# SCH_CyBorgSPP.net
KiCad netlist of a schematic drawn in EasyEDA
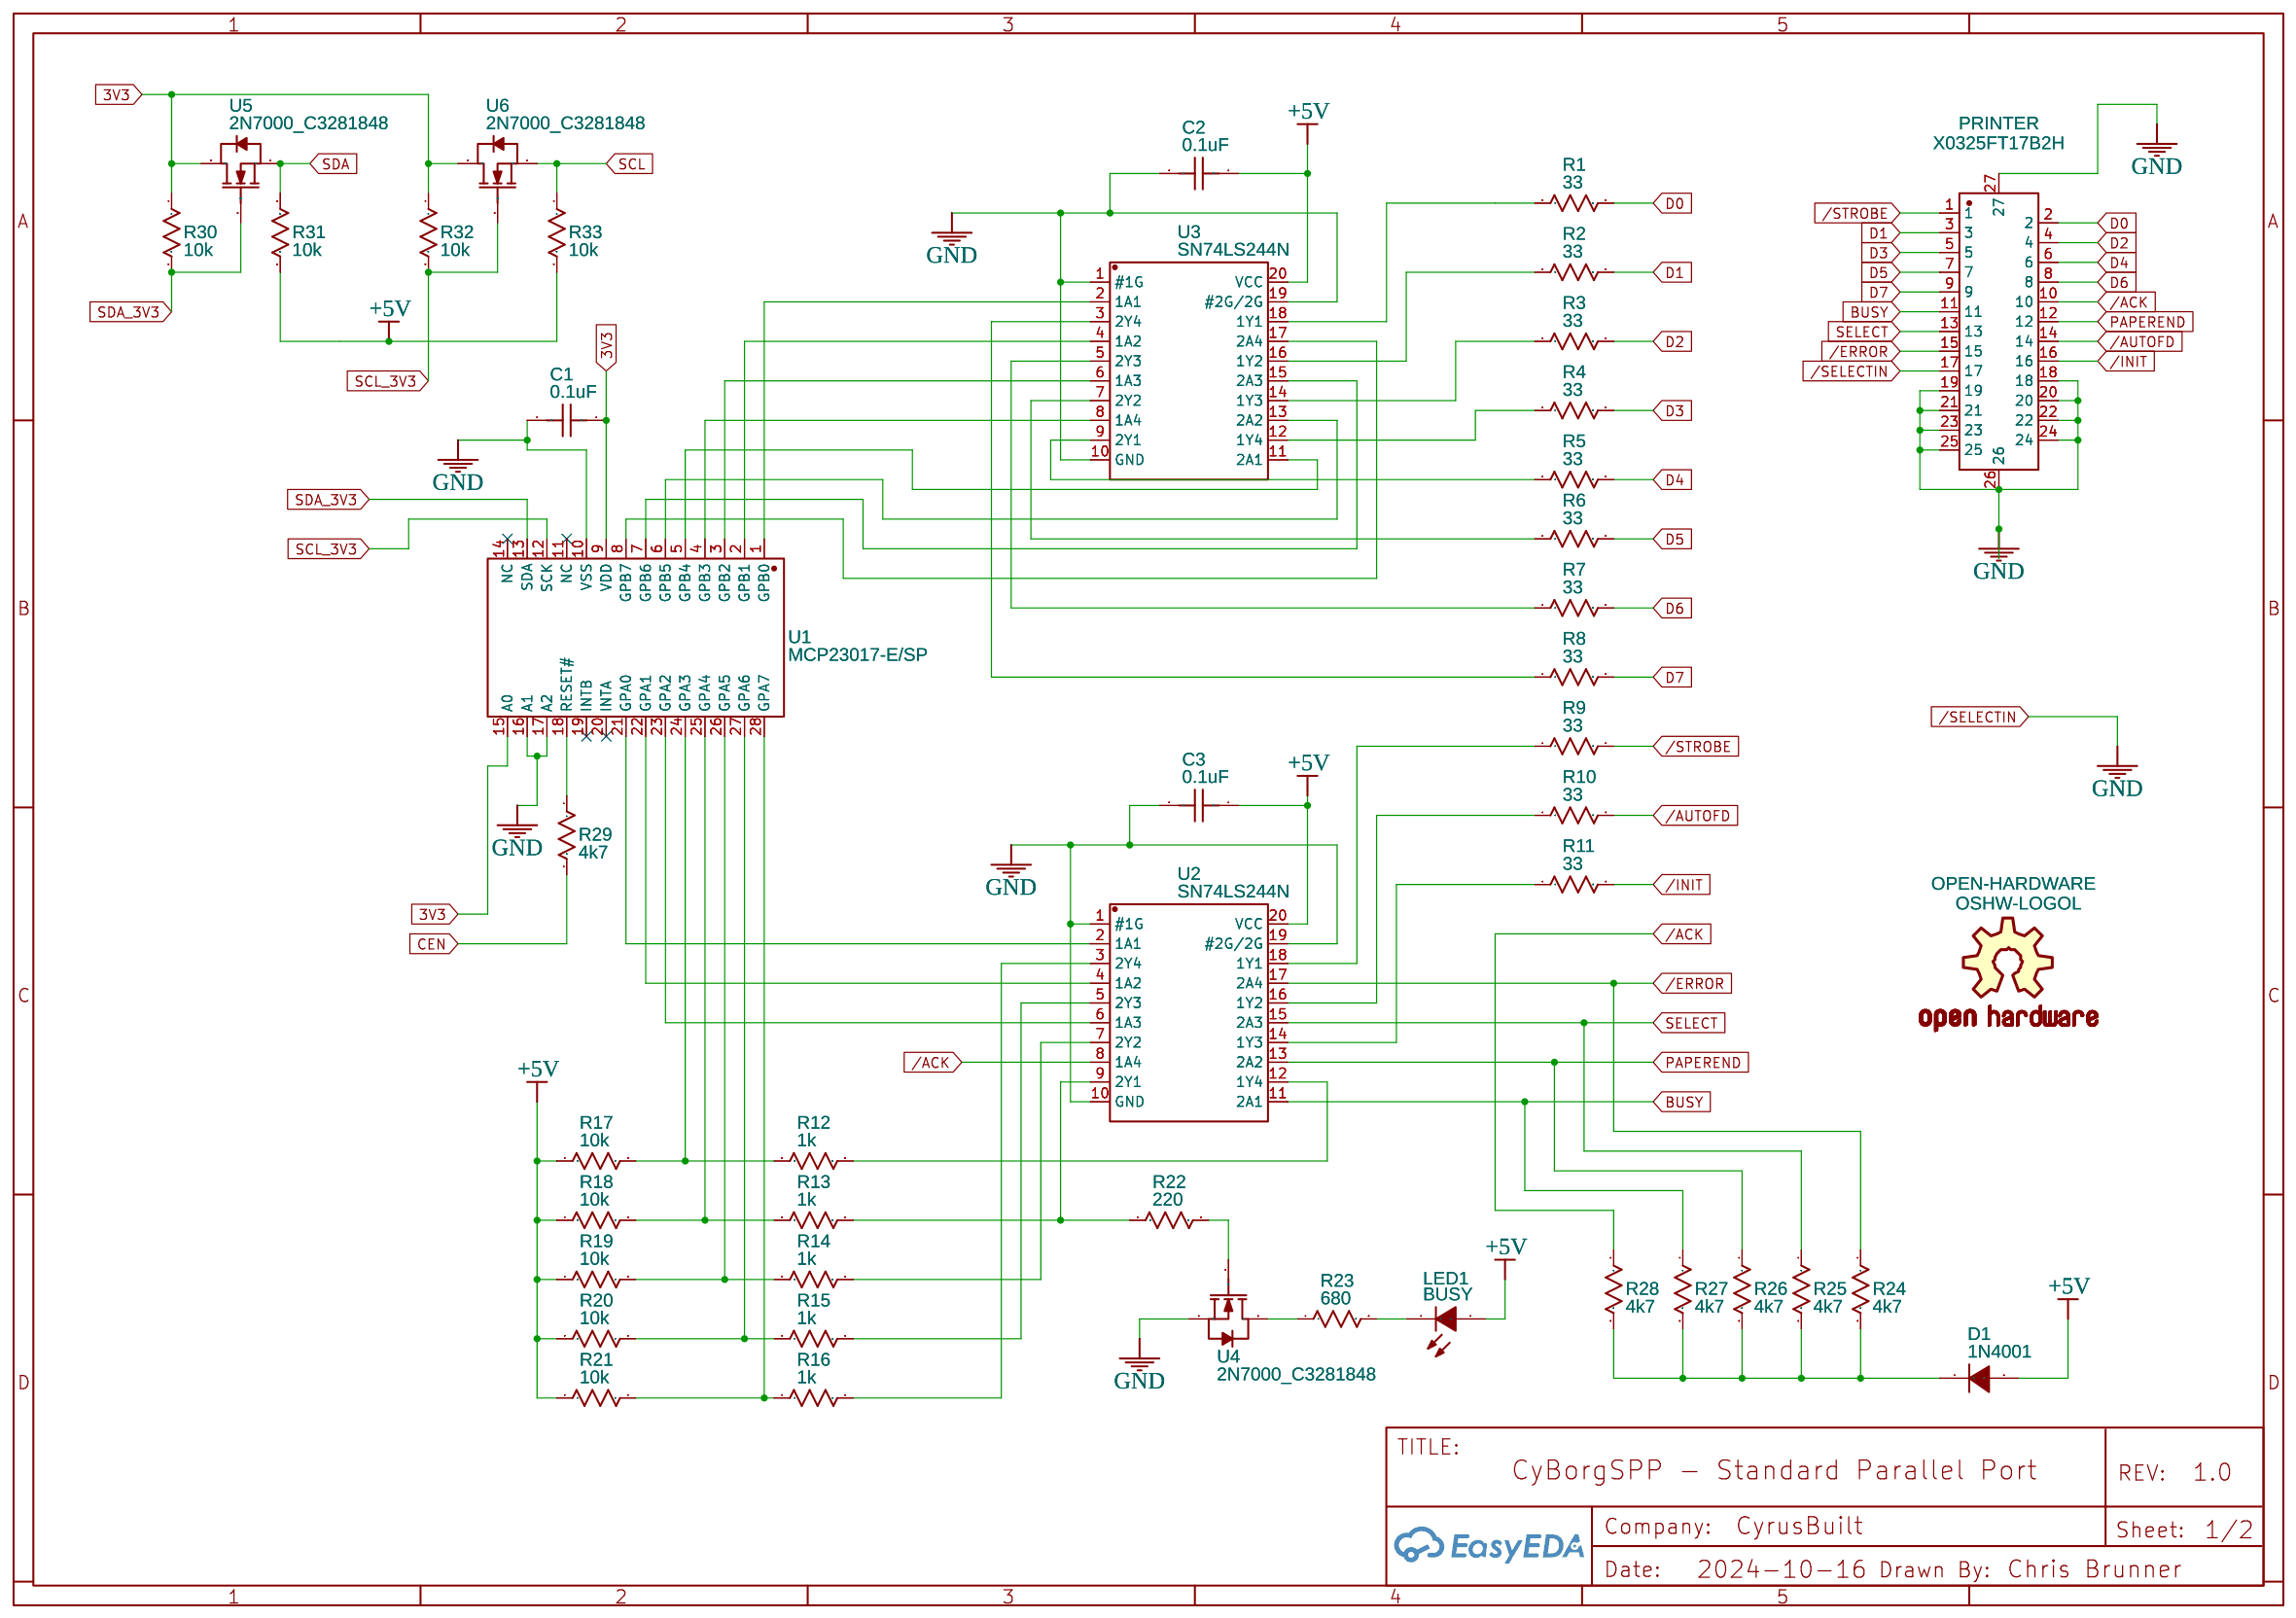
[diagram p0: CyBorgSPP]
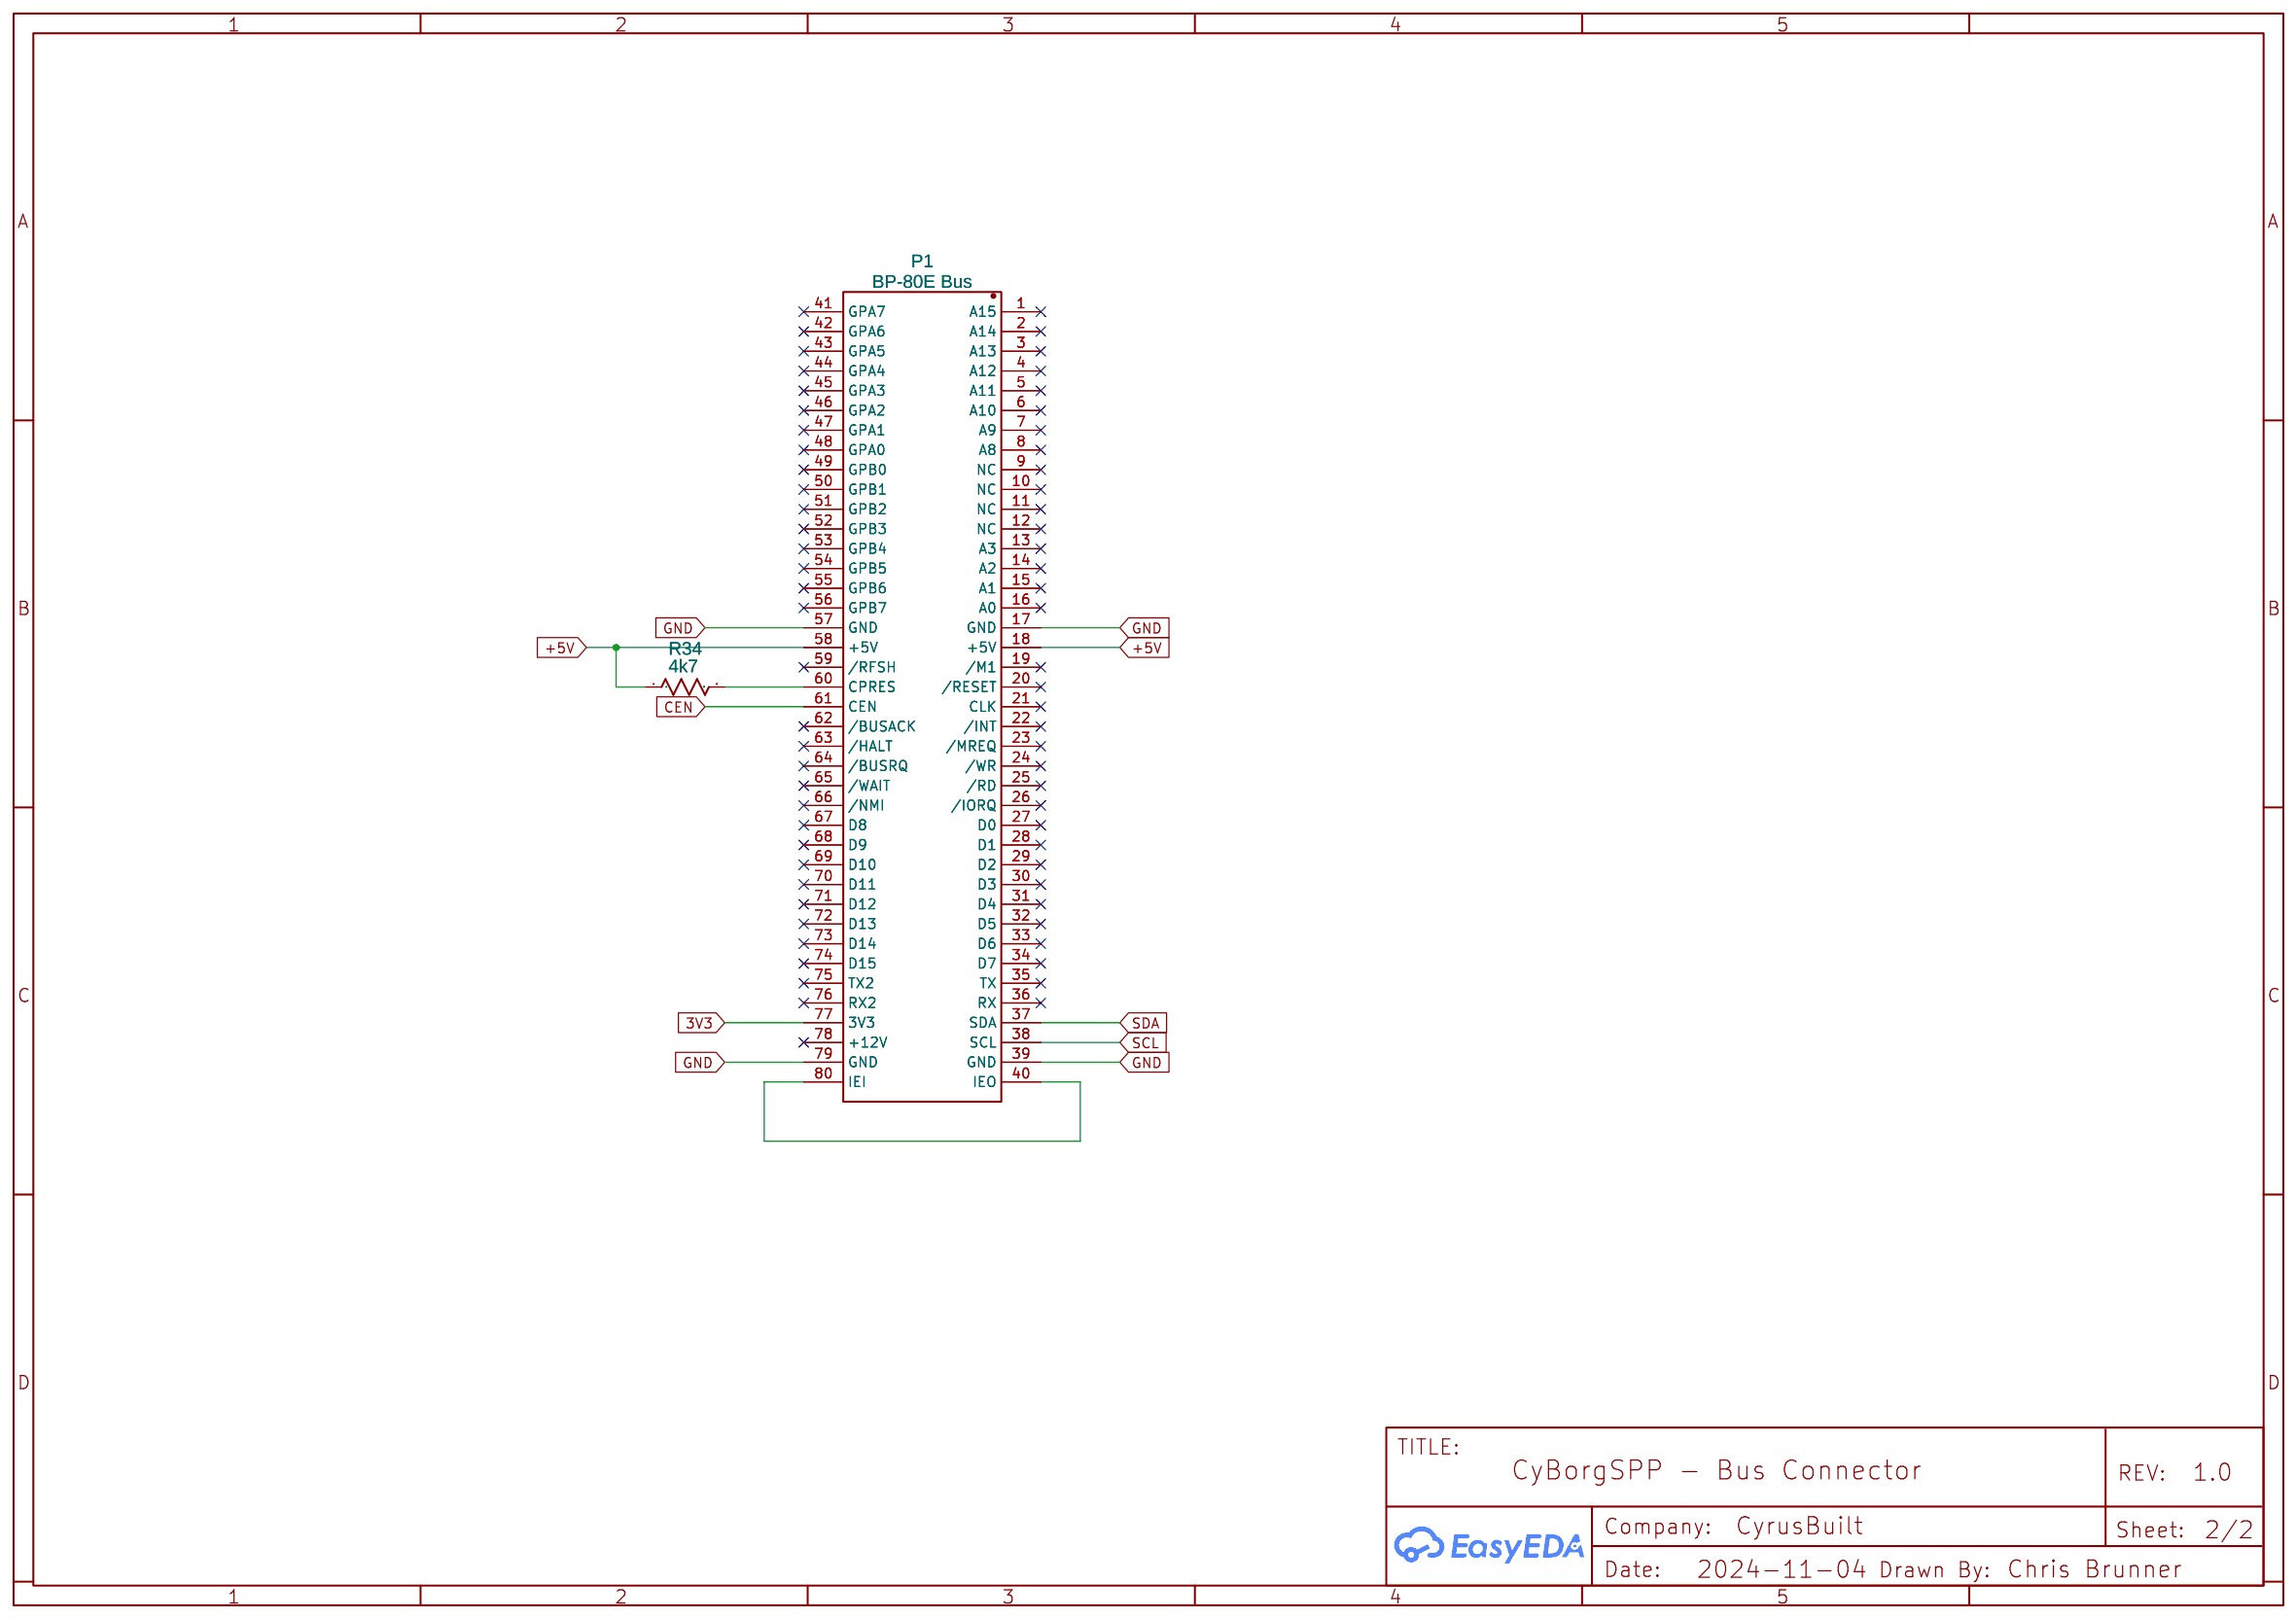
[diagram p1: CyBorgSPP_Bus]

(export (version "E")
  (design (tool "Eeschema 10.0.6"))
  (components
    (comp (ref "C1") (value "0.1uF") (libsource (lib "") (part "C_0603_US")))
    (comp (ref "C2") (value "0.1uF") (libsource (lib "") (part "C_0603_US")))
    (comp (ref "C3") (value "0.1uF") (libsource (lib "") (part "C_0603_US")))
    (comp (ref "D1")
      (value "1N4001")
      (fields (field (name "Manufacturer") "LRC"))
      (libsource (lib "") (part "1N4001"))
    )
    (comp (ref "LED1")
      (value "BUSY")
      (fields
        (field (name "Manufacturer Part") "204-10SURD/S530-A3")
        (field (name "Manufacturer") "EVERLIGHT(亿光)")
      )
      (libsource (lib "") (part "204-10SURD/S530-A3"))
    )
    (comp (ref "OPEN-HARDWARE") (value "OSHW-LOGOL") (libsource (lib "") (part "OSHW-LOGOL")))
    (comp (ref "PRINTER")
      (value "X0325FT17B2H")
      (fields (field (name "Manufacturer") "XKB Connectivity(中国星坤)"))
      (libsource (lib "") (part "X0325FT17B2H"))
    )
    (comp (ref "R1")
      (value "33")
      (fields (field (name "Manufacturer Part") "MCF 0.25W 150R") (field (name "Manufacturer") "MULTICOMP"))
      (libsource (lib "") (part "MCF 0.25W 150R"))
    )
    (comp (ref "R2")
      (value "33")
      (fields (field (name "Manufacturer Part") "MCF 0.25W 150R") (field (name "Manufacturer") "MULTICOMP"))
      (libsource (lib "") (part "MCF 0.25W 150R"))
    )
    (comp (ref "R3")
      (value "33")
      (fields (field (name "Manufacturer Part") "MCF 0.25W 150R") (field (name "Manufacturer") "MULTICOMP"))
      (libsource (lib "") (part "MCF 0.25W 150R"))
    )
    (comp (ref "R4")
      (value "33")
      (fields (field (name "Manufacturer Part") "MCF 0.25W 150R") (field (name "Manufacturer") "MULTICOMP"))
      (libsource (lib "") (part "MCF 0.25W 150R"))
    )
    (comp (ref "R5")
      (value "33")
      (fields (field (name "Manufacturer Part") "MCF 0.25W 150R") (field (name "Manufacturer") "MULTICOMP"))
      (libsource (lib "") (part "MCF 0.25W 150R"))
    )
    (comp (ref "R6")
      (value "33")
      (fields (field (name "Manufacturer Part") "MCF 0.25W 150R") (field (name "Manufacturer") "MULTICOMP"))
      (libsource (lib "") (part "MCF 0.25W 150R"))
    )
    (comp (ref "R7")
      (value "33")
      (fields (field (name "Manufacturer Part") "MCF 0.25W 150R") (field (name "Manufacturer") "MULTICOMP"))
      (libsource (lib "") (part "MCF 0.25W 150R"))
    )
    (comp (ref "R8")
      (value "33")
      (fields (field (name "Manufacturer Part") "MCF 0.25W 150R") (field (name "Manufacturer") "MULTICOMP"))
      (libsource (lib "") (part "MCF 0.25W 150R"))
    )
    (comp (ref "R9")
      (value "33")
      (fields (field (name "Manufacturer Part") "MCF 0.25W 150R") (field (name "Manufacturer") "MULTICOMP"))
      (libsource (lib "") (part "MCF 0.25W 150R"))
    )
    (comp (ref "R10")
      (value "33")
      (fields (field (name "Manufacturer Part") "MCF 0.25W 150R") (field (name "Manufacturer") "MULTICOMP"))
      (libsource (lib "") (part "MCF 0.25W 150R"))
    )
    (comp (ref "R11")
      (value "33")
      (fields (field (name "Manufacturer Part") "MCF 0.25W 150R") (field (name "Manufacturer") "MULTICOMP"))
      (libsource (lib "") (part "MCF 0.25W 150R"))
    )
    (comp (ref "R12")
      (value "1k")
      (fields (field (name "Manufacturer Part") "MCF 0.25W 150R") (field (name "Manufacturer") "MULTICOMP"))
      (libsource (lib "") (part "MCF 0.25W 150R"))
    )
    (comp (ref "R13")
      (value "1k")
      (fields (field (name "Manufacturer Part") "MCF 0.25W 150R") (field (name "Manufacturer") "MULTICOMP"))
      (libsource (lib "") (part "MCF 0.25W 150R"))
    )
    (comp (ref "R14")
      (value "1k")
      (fields (field (name "Manufacturer Part") "MCF 0.25W 150R") (field (name "Manufacturer") "MULTICOMP"))
      (libsource (lib "") (part "MCF 0.25W 150R"))
    )
    (comp (ref "R15")
      (value "1k")
      (fields (field (name "Manufacturer Part") "MCF 0.25W 150R") (field (name "Manufacturer") "MULTICOMP"))
      (libsource (lib "") (part "MCF 0.25W 150R"))
    )
    (comp (ref "R16")
      (value "1k")
      (fields (field (name "Manufacturer Part") "MCF 0.25W 150R") (field (name "Manufacturer") "MULTICOMP"))
      (libsource (lib "") (part "MCF 0.25W 150R"))
    )
    (comp (ref "R17")
      (value "10k")
      (fields (field (name "Manufacturer Part") "MCF 0.25W 150R") (field (name "Manufacturer") "MULTICOMP"))
      (libsource (lib "") (part "MCF 0.25W 150R"))
    )
    (comp (ref "R18")
      (value "10k")
      (fields (field (name "Manufacturer Part") "MCF 0.25W 150R") (field (name "Manufacturer") "MULTICOMP"))
      (libsource (lib "") (part "MCF 0.25W 150R"))
    )
    (comp (ref "R19")
      (value "10k")
      (fields (field (name "Manufacturer Part") "MCF 0.25W 150R") (field (name "Manufacturer") "MULTICOMP"))
      (libsource (lib "") (part "MCF 0.25W 150R"))
    )
    (comp (ref "R20")
      (value "10k")
      (fields (field (name "Manufacturer Part") "MCF 0.25W 150R") (field (name "Manufacturer") "MULTICOMP"))
      (libsource (lib "") (part "MCF 0.25W 150R"))
    )
    (comp (ref "R21")
      (value "10k")
      (fields (field (name "Manufacturer Part") "MCF 0.25W 150R") (field (name "Manufacturer") "MULTICOMP"))
      (libsource (lib "") (part "MCF 0.25W 150R"))
    )
    (comp (ref "R22")
      (value "220")
      (fields (field (name "Manufacturer Part") "MCF 0.25W 150R") (field (name "Manufacturer") "MULTICOMP"))
      (libsource (lib "") (part "MCF 0.25W 150R"))
    )
    (comp (ref "R23")
      (value "680")
      (fields (field (name "Manufacturer Part") "MCF 0.25W 150R") (field (name "Manufacturer") "MULTICOMP"))
      (libsource (lib "") (part "MCF 0.25W 150R"))
    )
    (comp (ref "R24")
      (value "4k7")
      (fields (field (name "Manufacturer Part") "MCF 0.25W 150R") (field (name "Manufacturer") "MULTICOMP"))
      (libsource (lib "") (part "MCF 0.25W 150R_1"))
    )
    (comp (ref "R25")
      (value "4k7")
      (fields (field (name "Manufacturer Part") "MCF 0.25W 150R") (field (name "Manufacturer") "MULTICOMP"))
      (libsource (lib "") (part "MCF 0.25W 150R_1"))
    )
    (comp (ref "R26")
      (value "4k7")
      (fields (field (name "Manufacturer Part") "MCF 0.25W 150R") (field (name "Manufacturer") "MULTICOMP"))
      (libsource (lib "") (part "MCF 0.25W 150R_1"))
    )
    (comp (ref "R27")
      (value "4k7")
      (fields (field (name "Manufacturer Part") "MCF 0.25W 150R") (field (name "Manufacturer") "MULTICOMP"))
      (libsource (lib "") (part "MCF 0.25W 150R_1"))
    )
    (comp (ref "R28")
      (value "4k7")
      (fields (field (name "Manufacturer Part") "MCF 0.25W 150R") (field (name "Manufacturer") "MULTICOMP"))
      (libsource (lib "") (part "MCF 0.25W 150R_1"))
    )
    (comp (ref "R29")
      (value "4k7")
      (fields (field (name "Manufacturer Part") "MCF 0.25W 150R") (field (name "Manufacturer") "MULTICOMP"))
      (libsource (lib "") (part "MCF 0.25W 150R_1"))
    )
    (comp (ref "R30")
      (value "10k")
      (fields (field (name "Manufacturer Part") "MCF 0.25W 150R") (field (name "Manufacturer") "MULTICOMP"))
      (libsource (lib "") (part "MCF 0.25W 150R_1"))
    )
    (comp (ref "R31")
      (value "10k")
      (fields (field (name "Manufacturer Part") "MCF 0.25W 150R") (field (name "Manufacturer") "MULTICOMP"))
      (libsource (lib "") (part "MCF 0.25W 150R_1"))
    )
    (comp (ref "R32")
      (value "10k")
      (fields (field (name "Manufacturer Part") "MCF 0.25W 150R") (field (name "Manufacturer") "MULTICOMP"))
      (libsource (lib "") (part "MCF 0.25W 150R_1"))
    )
    (comp (ref "R33")
      (value "10k")
      (fields (field (name "Manufacturer Part") "MCF 0.25W 150R") (field (name "Manufacturer") "MULTICOMP"))
      (libsource (lib "") (part "MCF 0.25W 150R_1"))
    )
    (comp (ref "U1")
      (value "MCP23017-E/SP")
      (fields (field (name "Manufacturer") "Microchip Tech"))
      (libsource (lib "") (part "MCP23017-E/SP"))
    )
    (comp (ref "U2")
      (value "SN74LS244N")
      (fields (field (name "Manufacturer") "TI(德州仪器)"))
      (libsource (lib "") (part "SN74LS244N"))
    )
    (comp (ref "U3")
      (value "SN74LS244N")
      (fields (field (name "Manufacturer") "TI(德州仪器)"))
      (libsource (lib "") (part "SN74LS244N"))
    )
    (comp (ref "U4")
      (value "2N7000_C3281848")
      (fields (field (name "Manufacturer Part") "2N7000") (field (name "Manufacturer") "DIOTEC(德欧泰克)"))
      (libsource (lib "") (part "2N7000_C3281848_1"))
    )
    (comp (ref "U5")
      (value "2N7000_C3281848")
      (fields (field (name "Manufacturer Part") "2N7000") (field (name "Manufacturer") "DIOTEC(德欧泰克)"))
      (libsource (lib "") (part "2N7000_C3281848"))
    )
    (comp (ref "U6")
      (value "2N7000_C3281848")
      (fields (field (name "Manufacturer Part") "2N7000") (field (name "Manufacturer") "DIOTEC(德欧泰克)"))
      (libsource (lib "") (part "2N7000_C3281848"))
    )
    (comp (ref "P1")
      (value "BP-80E Bus")
      (fields
        (field (name "Manufacturer Part") "ReliaPro")
        (field (name "Manufacturer") "2.54mm 1x40T Female header")
      )
      (libsource (lib "") (part "Extended Backplane 2x40 Male Angled"))
    )
    (comp (ref "R34")
      (value "4k7")
      (fields (field (name "Manufacturer Part") "MCF 0.25W 150R") (field (name "Manufacturer") "MULTICOMP"))
      (libsource (lib "") (part "MCF 0.25W 150R"))
    )
  )
  (nets
    (net (code "1") (name "+5V") (class "Default")
      (node (ref "C2") (pin "1") (pinfunction "1_1") (pintype "unspecified"))
      (node (ref "C3") (pin "1") (pinfunction "1_1") (pintype "unspecified"))
      (node (ref "D1") (pin "2") (pinfunction "A_2") (pintype "unspecified"))
      (node (ref "LED1") (pin "1") (pinfunction "A_1") (pintype "input"))
      (node (ref "P1") (pin "18") (pinfunction "+5V_18") (pintype "unspecified"))
      (node (ref "P1") (pin "58") (pinfunction "+5V_58") (pintype "unspecified"))
      (node (ref "R17") (pin "1") (pinfunction "1_1") (pintype "unspecified"))
      (node (ref "R18") (pin "1") (pinfunction "1_1") (pintype "unspecified"))
      (node (ref "R19") (pin "1") (pinfunction "1_1") (pintype "unspecified"))
      (node (ref "R20") (pin "1") (pinfunction "1_1") (pintype "unspecified"))
      (node (ref "R21") (pin "1") (pinfunction "1_1") (pintype "unspecified"))
      (node (ref "R31") (pin "2") (pinfunction "2_2") (pintype "unspecified"))
      (node (ref "R33") (pin "2") (pinfunction "2_2") (pintype "unspecified"))
      (node (ref "R34") (pin "1") (pinfunction "1_1") (pintype "unspecified"))
      (node (ref "U2") (pin "20") (pinfunction "VCC_20") (pintype "unspecified"))
      (node (ref "U3") (pin "20") (pinfunction "VCC_20") (pintype "unspecified"))
    )
    (net (code "2") (name "3V3") (class "Default")
      (node (ref "C1") (pin "1") (pinfunction "1_1") (pintype "unspecified"))
      (node (ref "P1") (pin "77") (pinfunction "3V3_77") (pintype "unspecified"))
      (node (ref "R30") (pin "1") (pinfunction "1_1") (pintype "unspecified"))
      (node (ref "R32") (pin "1") (pinfunction "1_1") (pintype "unspecified"))
      (node (ref "U1") (pin "15") (pinfunction "A0_15") (pintype "unspecified"))
      (node (ref "U1") (pin "9") (pinfunction "VDD_9") (pintype "unspecified"))
      (node (ref "U5") (pin "3") (pinfunction "D_3") (pintype "unspecified"))
      (node (ref "U6") (pin "3") (pinfunction "D_3") (pintype "unspecified"))
    )
    (net (code "3") (name "BUSY") (class "Default")
      (node (ref "PRINTER") (pin "11") (pinfunction "11_11") (pintype "unspecified"))
      (node (ref "R27") (pin "1") (pinfunction "1_1") (pintype "unspecified"))
      (node (ref "U2") (pin "11") (pinfunction "2A1_11") (pintype "unspecified"))
    )
    (net (code "4") (name "CEN") (class "Default")
      (node (ref "P1") (pin "61") (pinfunction "CEN_61") (pintype "unspecified"))
      (node (ref "R29") (pin "2") (pinfunction "2_2") (pintype "unspecified"))
    )
    (net (code "5") (name "D0") (class "Default")
      (node (ref "PRINTER") (pin "2") (pinfunction "2_2") (pintype "unspecified"))
      (node (ref "R1") (pin "2") (pinfunction "2_2") (pintype "unspecified"))
    )
    (net (code "6") (name "D1") (class "Default")
      (node (ref "PRINTER") (pin "3") (pinfunction "3_3") (pintype "unspecified"))
      (node (ref "R2") (pin "2") (pinfunction "2_2") (pintype "unspecified"))
    )
    (net (code "7") (name "D2") (class "Default")
      (node (ref "PRINTER") (pin "4") (pinfunction "4_4") (pintype "unspecified"))
      (node (ref "R3") (pin "2") (pinfunction "2_2") (pintype "unspecified"))
    )
    (net (code "8") (name "D3") (class "Default")
      (node (ref "PRINTER") (pin "5") (pinfunction "5_5") (pintype "unspecified"))
      (node (ref "R4") (pin "2") (pinfunction "2_2") (pintype "unspecified"))
    )
    (net (code "9") (name "D4") (class "Default")
      (node (ref "PRINTER") (pin "6") (pinfunction "6_6") (pintype "unspecified"))
      (node (ref "R5") (pin "2") (pinfunction "2_2") (pintype "unspecified"))
    )
    (net (code "10") (name "D5") (class "Default")
      (node (ref "PRINTER") (pin "7") (pinfunction "7_7") (pintype "unspecified"))
      (node (ref "R6") (pin "2") (pinfunction "2_2") (pintype "unspecified"))
    )
    (net (code "11") (name "D6") (class "Default")
      (node (ref "PRINTER") (pin "8") (pinfunction "8_8") (pintype "unspecified"))
      (node (ref "R7") (pin "2") (pinfunction "2_2") (pintype "unspecified"))
    )
    (net (code "12") (name "D7") (class "Default")
      (node (ref "PRINTER") (pin "9") (pinfunction "9_9") (pintype "unspecified"))
      (node (ref "R8") (pin "2") (pinfunction "2_2") (pintype "unspecified"))
    )
    (net (code "13") (name "GND") (class "Default")
      (node (ref "C1") (pin "2") (pinfunction "2_2") (pintype "unspecified"))
      (node (ref "C2") (pin "2") (pinfunction "2_2") (pintype "unspecified"))
      (node (ref "C3") (pin "2") (pinfunction "2_2") (pintype "unspecified"))
      (node (ref "P1") (pin "17") (pinfunction "GND_17") (pintype "unspecified"))
      (node (ref "P1") (pin "39") (pinfunction "GND_39") (pintype "unspecified"))
      (node (ref "P1") (pin "57") (pinfunction "GND_57") (pintype "unspecified"))
      (node (ref "P1") (pin "79") (pinfunction "GND_79") (pintype "unspecified"))
      (node (ref "PRINTER") (pin "17") (pinfunction "17_17") (pintype "unspecified"))
      (node (ref "PRINTER") (pin "18") (pinfunction "18_18") (pintype "unspecified"))
      (node (ref "PRINTER") (pin "19") (pinfunction "19_19") (pintype "unspecified"))
      (node (ref "PRINTER") (pin "20") (pinfunction "20_20") (pintype "unspecified"))
      (node (ref "PRINTER") (pin "21") (pinfunction "21_21") (pintype "unspecified"))
      (node (ref "PRINTER") (pin "22") (pinfunction "22_22") (pintype "unspecified"))
      (node (ref "PRINTER") (pin "23") (pinfunction "23_23") (pintype "unspecified"))
      (node (ref "PRINTER") (pin "24") (pinfunction "24_24") (pintype "unspecified"))
      (node (ref "PRINTER") (pin "25") (pinfunction "25_25") (pintype "unspecified"))
      (node (ref "PRINTER") (pin "26") (pinfunction "26_26") (pintype "unspecified"))
      (node (ref "PRINTER") (pin "27") (pinfunction "27_27") (pintype "unspecified"))
      (node (ref "U1") (pin "10") (pinfunction "VSS_10") (pintype "unspecified"))
      (node (ref "U1") (pin "16") (pinfunction "A1_16") (pintype "unspecified"))
      (node (ref "U1") (pin "17") (pinfunction "A2_17") (pintype "unspecified"))
      (node (ref "U2") (pin "1") (pinfunction "#1G_1") (pintype "unspecified"))
      (node (ref "U2") (pin "10") (pinfunction "GND_10") (pintype "unspecified"))
      (node (ref "U2") (pin "19") (pinfunction "#2G/2G_19") (pintype "unspecified"))
      (node (ref "U3") (pin "1") (pinfunction "#1G_1") (pintype "unspecified"))
      (node (ref "U3") (pin "10") (pinfunction "GND_10") (pintype "unspecified"))
      (node (ref "U3") (pin "19") (pinfunction "#2G/2G_19") (pintype "unspecified"))
      (node (ref "U4") (pin "1") (pinfunction "S_1") (pintype "unspecified"))
    )
    (net (code "14") (name "Net-(D1-K)") (class "Default")
      (node (ref "D1") (pin "1") (pinfunction "K_1") (pintype "unspecified"))
      (node (ref "R24") (pin "2") (pinfunction "2_2") (pintype "unspecified"))
      (node (ref "R25") (pin "2") (pinfunction "2_2") (pintype "unspecified"))
      (node (ref "R26") (pin "2") (pinfunction "2_2") (pintype "unspecified"))
      (node (ref "R27") (pin "2") (pinfunction "2_2") (pintype "unspecified"))
      (node (ref "R28") (pin "2") (pinfunction "2_2") (pintype "unspecified"))
    )
    (net (code "15") (name "Net-(LED1-K)") (class "Default")
      (node (ref "LED1") (pin "2") (pinfunction "K_2") (pintype "input"))
      (node (ref "R23") (pin "2") (pinfunction "2_2") (pintype "unspecified"))
    )
    (net (code "16") (name "Net-(P1-CPRES)") (class "Default")
      (node (ref "P1") (pin "60") (pinfunction "CPRES_60") (pintype "unspecified"))
      (node (ref "R34") (pin "2") (pinfunction "2_2") (pintype "unspecified"))
    )
    (net (code "17") (name "Net-(P1-IEI)") (class "Default")
      (node (ref "P1") (pin "40") (pinfunction "IEO_40") (pintype "unspecified"))
      (node (ref "P1") (pin "80") (pinfunction "IEI_80") (pintype "unspecified"))
    )
    (net (code "18") (name "Net-(U1-GPA0)") (class "Default")
      (node (ref "U1") (pin "21") (pinfunction "GPA0_21") (pintype "unspecified"))
      (node (ref "U2") (pin "2") (pinfunction "1A1_2") (pintype "unspecified"))
    )
    (net (code "19") (name "Net-(U1-GPA1)") (class "Default")
      (node (ref "U1") (pin "22") (pinfunction "GPA1_22") (pintype "unspecified"))
      (node (ref "U2") (pin "4") (pinfunction "1A2_4") (pintype "unspecified"))
    )
    (net (code "20") (name "Net-(U1-GPA2)") (class "Default")
      (node (ref "U1") (pin "23") (pinfunction "GPA2_23") (pintype "unspecified"))
      (node (ref "U2") (pin "6") (pinfunction "1A3_6") (pintype "unspecified"))
    )
    (net (code "21") (name "Net-(U1-GPA3)") (class "Default")
      (node (ref "R12") (pin "1") (pinfunction "1_1") (pintype "unspecified"))
      (node (ref "R17") (pin "2") (pinfunction "2_2") (pintype "unspecified"))
      (node (ref "U1") (pin "24") (pinfunction "GPA3_24") (pintype "unspecified"))
    )
    (net (code "22") (name "Net-(U1-GPA4)") (class "Default")
      (node (ref "R13") (pin "1") (pinfunction "1_1") (pintype "unspecified"))
      (node (ref "R18") (pin "2") (pinfunction "2_2") (pintype "unspecified"))
      (node (ref "U1") (pin "25") (pinfunction "GPA4_25") (pintype "unspecified"))
    )
    (net (code "23") (name "Net-(U1-GPA5)") (class "Default")
      (node (ref "R14") (pin "1") (pinfunction "1_1") (pintype "unspecified"))
      (node (ref "R19") (pin "2") (pinfunction "2_2") (pintype "unspecified"))
      (node (ref "U1") (pin "26") (pinfunction "GPA5_26") (pintype "unspecified"))
    )
    (net (code "24") (name "Net-(U1-GPA6)") (class "Default")
      (node (ref "R15") (pin "1") (pinfunction "1_1") (pintype "unspecified"))
      (node (ref "R20") (pin "2") (pinfunction "2_2") (pintype "unspecified"))
      (node (ref "U1") (pin "27") (pinfunction "GPA6_27") (pintype "unspecified"))
    )
    (net (code "25") (name "Net-(U1-GPA7)") (class "Default")
      (node (ref "R16") (pin "1") (pinfunction "1_1") (pintype "unspecified"))
      (node (ref "R21") (pin "2") (pinfunction "2_2") (pintype "unspecified"))
      (node (ref "U1") (pin "28") (pinfunction "GPA7_28") (pintype "unspecified"))
    )
    (net (code "26") (name "Net-(U1-GPB0)") (class "Default")
      (node (ref "U1") (pin "1") (pinfunction "GPB0_1") (pintype "unspecified"))
      (node (ref "U3") (pin "2") (pinfunction "1A1_2") (pintype "unspecified"))
    )
    (net (code "27") (name "Net-(U1-GPB1)") (class "Default")
      (node (ref "U1") (pin "2") (pinfunction "GPB1_2") (pintype "unspecified"))
      (node (ref "U3") (pin "4") (pinfunction "1A2_4") (pintype "unspecified"))
    )
    (net (code "28") (name "Net-(U1-GPB2)") (class "Default")
      (node (ref "U1") (pin "3") (pinfunction "GPB2_3") (pintype "unspecified"))
      (node (ref "U3") (pin "6") (pinfunction "1A3_6") (pintype "unspecified"))
    )
    (net (code "29") (name "Net-(U1-GPB3)") (class "Default")
      (node (ref "U1") (pin "4") (pinfunction "GPB3_4") (pintype "unspecified"))
      (node (ref "U3") (pin "8") (pinfunction "1A4_8") (pintype "unspecified"))
    )
    (net (code "30") (name "Net-(U1-GPB4)") (class "Default")
      (node (ref "U1") (pin "5") (pinfunction "GPB4_5") (pintype "unspecified"))
      (node (ref "U3") (pin "11") (pinfunction "2A1_11") (pintype "unspecified"))
    )
    (net (code "31") (name "Net-(U1-GPB5)") (class "Default")
      (node (ref "U1") (pin "6") (pinfunction "GPB5_6") (pintype "unspecified"))
      (node (ref "U3") (pin "13") (pinfunction "2A2_13") (pintype "unspecified"))
    )
    (net (code "32") (name "Net-(U1-GPB6)") (class "Default")
      (node (ref "U1") (pin "7") (pinfunction "GPB6_7") (pintype "unspecified"))
      (node (ref "U3") (pin "15") (pinfunction "2A3_15") (pintype "unspecified"))
    )
    (net (code "33") (name "Net-(U1-GPB7)") (class "Default")
      (node (ref "U1") (pin "8") (pinfunction "GPB7_8") (pintype "unspecified"))
      (node (ref "U3") (pin "17") (pinfunction "2A4_17") (pintype "unspecified"))
    )
    (net (code "34") (name "Net-(U1-RESET#)") (class "Default")
      (node (ref "R29") (pin "1") (pinfunction "1_1") (pintype "unspecified"))
      (node (ref "U1") (pin "18") (pinfunction "RESET#_18") (pintype "unspecified"))
    )
    (net (code "35") (name "Net-(U2-1Y1)") (class "Default")
      (node (ref "R9") (pin "1") (pinfunction "1_1") (pintype "unspecified"))
      (node (ref "U2") (pin "18") (pinfunction "1Y1_18") (pintype "unspecified"))
    )
    (net (code "36") (name "Net-(U2-1Y2)") (class "Default")
      (node (ref "R10") (pin "1") (pinfunction "1_1") (pintype "unspecified"))
      (node (ref "U2") (pin "16") (pinfunction "1Y2_16") (pintype "unspecified"))
    )
    (net (code "37") (name "Net-(U2-1Y3)") (class "Default")
      (node (ref "R11") (pin "1") (pinfunction "1_1") (pintype "unspecified"))
      (node (ref "U2") (pin "14") (pinfunction "1Y3_14") (pintype "unspecified"))
    )
    (net (code "38") (name "Net-(U2-1Y4)") (class "Default")
      (node (ref "R12") (pin "2") (pinfunction "2_2") (pintype "unspecified"))
      (node (ref "U2") (pin "12") (pinfunction "1Y4_12") (pintype "unspecified"))
    )
    (net (code "39") (name "Net-(U2-2Y1)") (class "Default")
      (node (ref "R13") (pin "2") (pinfunction "2_2") (pintype "unspecified"))
      (node (ref "R22") (pin "1") (pinfunction "1_1") (pintype "unspecified"))
      (node (ref "U2") (pin "9") (pinfunction "2Y1_9") (pintype "unspecified"))
    )
    (net (code "40") (name "Net-(U2-2Y2)") (class "Default")
      (node (ref "R14") (pin "2") (pinfunction "2_2") (pintype "unspecified"))
      (node (ref "U2") (pin "7") (pinfunction "2Y2_7") (pintype "unspecified"))
    )
    (net (code "41") (name "Net-(U2-2Y3)") (class "Default")
      (node (ref "R15") (pin "2") (pinfunction "2_2") (pintype "unspecified"))
      (node (ref "U2") (pin "5") (pinfunction "2Y3_5") (pintype "unspecified"))
    )
    (net (code "42") (name "Net-(U2-2Y4)") (class "Default")
      (node (ref "R16") (pin "2") (pinfunction "2_2") (pintype "unspecified"))
      (node (ref "U2") (pin "3") (pinfunction "2Y4_3") (pintype "unspecified"))
    )
    (net (code "43") (name "Net-(U3-1Y1)") (class "Default")
      (node (ref "R1") (pin "1") (pinfunction "1_1") (pintype "unspecified"))
      (node (ref "U3") (pin "18") (pinfunction "1Y1_18") (pintype "unspecified"))
    )
    (net (code "44") (name "Net-(U3-1Y2)") (class "Default")
      (node (ref "R2") (pin "1") (pinfunction "1_1") (pintype "unspecified"))
      (node (ref "U3") (pin "16") (pinfunction "1Y2_16") (pintype "unspecified"))
    )
    (net (code "45") (name "Net-(U3-1Y3)") (class "Default")
      (node (ref "R3") (pin "1") (pinfunction "1_1") (pintype "unspecified"))
      (node (ref "U3") (pin "14") (pinfunction "1Y3_14") (pintype "unspecified"))
    )
    (net (code "46") (name "Net-(U3-1Y4)") (class "Default")
      (node (ref "R4") (pin "1") (pinfunction "1_1") (pintype "unspecified"))
      (node (ref "U3") (pin "12") (pinfunction "1Y4_12") (pintype "unspecified"))
    )
    (net (code "47") (name "Net-(U3-2Y1)") (class "Default")
      (node (ref "R5") (pin "1") (pinfunction "1_1") (pintype "unspecified"))
      (node (ref "U3") (pin "9") (pinfunction "2Y1_9") (pintype "unspecified"))
    )
    (net (code "48") (name "Net-(U3-2Y2)") (class "Default")
      (node (ref "R6") (pin "1") (pinfunction "1_1") (pintype "unspecified"))
      (node (ref "U3") (pin "7") (pinfunction "2Y2_7") (pintype "unspecified"))
    )
    (net (code "49") (name "Net-(U3-2Y3)") (class "Default")
      (node (ref "R7") (pin "1") (pinfunction "1_1") (pintype "unspecified"))
      (node (ref "U3") (pin "5") (pinfunction "2Y3_5") (pintype "unspecified"))
    )
    (net (code "50") (name "Net-(U3-2Y4)") (class "Default")
      (node (ref "R8") (pin "1") (pinfunction "1_1") (pintype "unspecified"))
      (node (ref "U3") (pin "3") (pinfunction "2Y4_3") (pintype "unspecified"))
    )
    (net (code "51") (name "Net-(U4-D)") (class "Default")
      (node (ref "R23") (pin "1") (pinfunction "1_1") (pintype "unspecified"))
      (node (ref "U4") (pin "3") (pinfunction "D_3") (pintype "unspecified"))
    )
    (net (code "52") (name "Net-(U4-G)") (class "Default")
      (node (ref "R22") (pin "2") (pinfunction "2_2") (pintype "unspecified"))
      (node (ref "U4") (pin "2") (pinfunction "G_2") (pintype "unspecified"))
    )
    (net (code "53") (name "PAPEREND") (class "Default")
      (node (ref "PRINTER") (pin "12") (pinfunction "12_12") (pintype "unspecified"))
      (node (ref "R26") (pin "1") (pinfunction "1_1") (pintype "unspecified"))
      (node (ref "U2") (pin "13") (pinfunction "2A2_13") (pintype "unspecified"))
    )
    (net (code "54") (name "SCL") (class "Default")
      (node (ref "P1") (pin "38") (pinfunction "SCL_38") (pintype "unspecified"))
      (node (ref "R33") (pin "1") (pinfunction "1_1") (pintype "unspecified"))
      (node (ref "U6") (pin "1") (pinfunction "S_1") (pintype "unspecified"))
    )
    (net (code "55") (name "SCL_3V3") (class "Default")
      (node (ref "R32") (pin "2") (pinfunction "2_2") (pintype "unspecified"))
      (node (ref "U1") (pin "12") (pinfunction "SCK_12") (pintype "unspecified"))
      (node (ref "U6") (pin "2") (pinfunction "G_2") (pintype "unspecified"))
    )
    (net (code "56") (name "SDA") (class "Default")
      (node (ref "P1") (pin "37") (pinfunction "SDA_37") (pintype "unspecified"))
      (node (ref "R31") (pin "1") (pinfunction "1_1") (pintype "unspecified"))
      (node (ref "U5") (pin "1") (pinfunction "S_1") (pintype "unspecified"))
    )
    (net (code "57") (name "SDA_3V3") (class "Default")
      (node (ref "R30") (pin "2") (pinfunction "2_2") (pintype "unspecified"))
      (node (ref "U1") (pin "13") (pinfunction "SDA_13") (pintype "unspecified"))
      (node (ref "U5") (pin "2") (pinfunction "G_2") (pintype "unspecified"))
    )
    (net (code "58") (name "SELECT") (class "Default")
      (node (ref "PRINTER") (pin "13") (pinfunction "13_13") (pintype "unspecified"))
      (node (ref "R25") (pin "1") (pinfunction "1_1") (pintype "unspecified"))
      (node (ref "U2") (pin "15") (pinfunction "2A3_15") (pintype "unspecified"))
    )
    (net (code "59") (name "unconnected-(P1-+12V-Pad78)") (class "Default")
      (node (ref "P1") (pin "78") (pinfunction "+12V_78") (pintype "unspecified+no_connect"))
    )
    (net (code "60") (name "unconnected-(P1-A0-Pad16)") (class "Default")
      (node (ref "P1") (pin "16") (pinfunction "A0_16") (pintype "unspecified+no_connect"))
    )
    (net (code "61") (name "unconnected-(P1-A1-Pad15)") (class "Default")
      (node (ref "P1") (pin "15") (pinfunction "A1_15") (pintype "unspecified+no_connect"))
    )
    (net (code "62") (name "unconnected-(P1-A2-Pad14)") (class "Default")
      (node (ref "P1") (pin "14") (pinfunction "A2_14") (pintype "unspecified+no_connect"))
    )
    (net (code "63") (name "unconnected-(P1-A3-Pad13)") (class "Default")
      (node (ref "P1") (pin "13") (pinfunction "A3_13") (pintype "unspecified+no_connect"))
    )
    (net (code "64") (name "unconnected-(P1-A8-Pad8)") (class "Default")
      (node (ref "P1") (pin "8") (pinfunction "A8_8") (pintype "unspecified+no_connect"))
    )
    (net (code "65") (name "unconnected-(P1-A9-Pad7)") (class "Default")
      (node (ref "P1") (pin "7") (pinfunction "A9_7") (pintype "unspecified+no_connect"))
    )
    (net (code "66") (name "unconnected-(P1-A10-Pad6)") (class "Default")
      (node (ref "P1") (pin "6") (pinfunction "A10_6") (pintype "unspecified+no_connect"))
    )
    (net (code "67") (name "unconnected-(P1-A11-Pad5)") (class "Default")
      (node (ref "P1") (pin "5") (pinfunction "A11_5") (pintype "unspecified+no_connect"))
    )
    (net (code "68") (name "unconnected-(P1-A12-Pad4)") (class "Default")
      (node (ref "P1") (pin "4") (pinfunction "A12_4") (pintype "unspecified+no_connect"))
    )
    (net (code "69") (name "unconnected-(P1-A13-Pad3)") (class "Default")
      (node (ref "P1") (pin "3") (pinfunction "A13_3") (pintype "unspecified+no_connect"))
    )
    (net (code "70") (name "unconnected-(P1-A14-Pad2)") (class "Default")
      (node (ref "P1") (pin "2") (pinfunction "A14_2") (pintype "unspecified+no_connect"))
    )
    (net (code "71") (name "unconnected-(P1-A15-Pad1)") (class "Default")
      (node (ref "P1") (pin "1") (pinfunction "A15_1") (pintype "unspecified+no_connect"))
    )
    (net (code "72") (name "unconnected-(P1-CLK-Pad21)") (class "Default")
      (node (ref "P1") (pin "21") (pinfunction "CLK_21") (pintype "unspecified+no_connect"))
    )
    (net (code "73") (name "unconnected-(P1-D0-Pad27)") (class "Default")
      (node (ref "P1") (pin "27") (pinfunction "D0_27") (pintype "unspecified+no_connect"))
    )
    (net (code "74") (name "unconnected-(P1-D1-Pad28)") (class "Default")
      (node (ref "P1") (pin "28") (pinfunction "D1_28") (pintype "unspecified+no_connect"))
    )
    (net (code "75") (name "unconnected-(P1-D2-Pad29)") (class "Default")
      (node (ref "P1") (pin "29") (pinfunction "D2_29") (pintype "unspecified+no_connect"))
    )
    (net (code "76") (name "unconnected-(P1-D3-Pad30)") (class "Default")
      (node (ref "P1") (pin "30") (pinfunction "D3_30") (pintype "unspecified+no_connect"))
    )
    (net (code "77") (name "unconnected-(P1-D4-Pad31)") (class "Default")
      (node (ref "P1") (pin "31") (pinfunction "D4_31") (pintype "unspecified+no_connect"))
    )
    (net (code "78") (name "unconnected-(P1-D5-Pad32)") (class "Default")
      (node (ref "P1") (pin "32") (pinfunction "D5_32") (pintype "unspecified+no_connect"))
    )
    (net (code "79") (name "unconnected-(P1-D6-Pad33)") (class "Default")
      (node (ref "P1") (pin "33") (pinfunction "D6_33") (pintype "unspecified+no_connect"))
    )
    (net (code "80") (name "unconnected-(P1-D7-Pad34)") (class "Default")
      (node (ref "P1") (pin "34") (pinfunction "D7_34") (pintype "unspecified+no_connect"))
    )
    (net (code "81") (name "unconnected-(P1-D8-Pad67)") (class "Default")
      (node (ref "P1") (pin "67") (pinfunction "D8_67") (pintype "unspecified+no_connect"))
    )
    (net (code "82") (name "unconnected-(P1-D9-Pad68)") (class "Default")
      (node (ref "P1") (pin "68") (pinfunction "D9_68") (pintype "unspecified+no_connect"))
    )
    (net (code "83") (name "unconnected-(P1-D10-Pad69)") (class "Default")
      (node (ref "P1") (pin "69") (pinfunction "D10_69") (pintype "unspecified+no_connect"))
    )
    (net (code "84") (name "unconnected-(P1-D11-Pad70)") (class "Default")
      (node (ref "P1") (pin "70") (pinfunction "D11_70") (pintype "unspecified+no_connect"))
    )
    (net (code "85") (name "unconnected-(P1-D12-Pad71)") (class "Default")
      (node (ref "P1") (pin "71") (pinfunction "D12_71") (pintype "unspecified+no_connect"))
    )
    (net (code "86") (name "unconnected-(P1-D13-Pad72)") (class "Default")
      (node (ref "P1") (pin "72") (pinfunction "D13_72") (pintype "unspecified+no_connect"))
    )
    (net (code "87") (name "unconnected-(P1-D14-Pad73)") (class "Default")
      (node (ref "P1") (pin "73") (pinfunction "D14_73") (pintype "unspecified+no_connect"))
    )
    (net (code "88") (name "unconnected-(P1-D15-Pad74)") (class "Default")
      (node (ref "P1") (pin "74") (pinfunction "D15_74") (pintype "unspecified+no_connect"))
    )
    (net (code "89") (name "unconnected-(P1-GPA0-Pad48)") (class "Default")
      (node (ref "P1") (pin "48") (pinfunction "GPA0_48") (pintype "unspecified+no_connect"))
    )
    (net (code "90") (name "unconnected-(P1-GPA1-Pad47)") (class "Default")
      (node (ref "P1") (pin "47") (pinfunction "GPA1_47") (pintype "unspecified+no_connect"))
    )
    (net (code "91") (name "unconnected-(P1-GPA2-Pad46)") (class "Default")
      (node (ref "P1") (pin "46") (pinfunction "GPA2_46") (pintype "unspecified+no_connect"))
    )
    (net (code "92") (name "unconnected-(P1-GPA3-Pad45)") (class "Default")
      (node (ref "P1") (pin "45") (pinfunction "GPA3_45") (pintype "unspecified+no_connect"))
    )
    (net (code "93") (name "unconnected-(P1-GPA4-Pad44)") (class "Default")
      (node (ref "P1") (pin "44") (pinfunction "GPA4_44") (pintype "unspecified+no_connect"))
    )
    (net (code "94") (name "unconnected-(P1-GPA5-Pad43)") (class "Default")
      (node (ref "P1") (pin "43") (pinfunction "GPA5_43") (pintype "unspecified+no_connect"))
    )
    (net (code "95") (name "unconnected-(P1-GPA6-Pad42)") (class "Default")
      (node (ref "P1") (pin "42") (pinfunction "GPA6_42") (pintype "unspecified+no_connect"))
    )
    (net (code "96") (name "unconnected-(P1-GPA7-Pad41)") (class "Default")
      (node (ref "P1") (pin "41") (pinfunction "GPA7_41") (pintype "unspecified+no_connect"))
    )
    (net (code "97") (name "unconnected-(P1-GPB0-Pad49)") (class "Default")
      (node (ref "P1") (pin "49") (pinfunction "GPB0_49") (pintype "unspecified+no_connect"))
    )
    (net (code "98") (name "unconnected-(P1-GPB1-Pad50)") (class "Default")
      (node (ref "P1") (pin "50") (pinfunction "GPB1_50") (pintype "unspecified+no_connect"))
    )
    (net (code "99") (name "unconnected-(P1-GPB2-Pad51)") (class "Default")
      (node (ref "P1") (pin "51") (pinfunction "GPB2_51") (pintype "unspecified+no_connect"))
    )
    (net (code "100") (name "unconnected-(P1-GPB3-Pad52)") (class "Default")
      (node (ref "P1") (pin "52") (pinfunction "GPB3_52") (pintype "unspecified+no_connect"))
    )
    (net (code "101") (name "unconnected-(P1-GPB4-Pad53)") (class "Default")
      (node (ref "P1") (pin "53") (pinfunction "GPB4_53") (pintype "unspecified+no_connect"))
    )
    (net (code "102") (name "unconnected-(P1-GPB5-Pad54)") (class "Default")
      (node (ref "P1") (pin "54") (pinfunction "GPB5_54") (pintype "unspecified+no_connect"))
    )
    (net (code "103") (name "unconnected-(P1-GPB6-Pad55)") (class "Default")
      (node (ref "P1") (pin "55") (pinfunction "GPB6_55") (pintype "unspecified+no_connect"))
    )
    (net (code "104") (name "unconnected-(P1-GPB7-Pad56)") (class "Default")
      (node (ref "P1") (pin "56") (pinfunction "GPB7_56") (pintype "unspecified+no_connect"))
    )
    (net (code "105") (name "unconnected-(P1-NC-Pad9)") (class "Default")
      (node (ref "P1") (pin "9") (pinfunction "NC_9") (pintype "unspecified+no_connect"))
    )
    (net (code "106") (name "unconnected-(P1-NC-Pad10)") (class "Default")
      (node (ref "P1") (pin "10") (pinfunction "NC_10") (pintype "unspecified+no_connect"))
    )
    (net (code "107") (name "unconnected-(P1-NC-Pad11)") (class "Default")
      (node (ref "P1") (pin "11") (pinfunction "NC_11") (pintype "unspecified+no_connect"))
    )
    (net (code "108") (name "unconnected-(P1-NC-Pad12)") (class "Default")
      (node (ref "P1") (pin "12") (pinfunction "NC_12") (pintype "unspecified+no_connect"))
    )
    (net (code "109") (name "unconnected-(P1-RX-Pad36)") (class "Default")
      (node (ref "P1") (pin "36") (pinfunction "RX_36") (pintype "unspecified+no_connect"))
    )
    (net (code "110") (name "unconnected-(P1-RX2-Pad76)") (class "Default")
      (node (ref "P1") (pin "76") (pinfunction "RX2_76") (pintype "unspecified+no_connect"))
    )
    (net (code "111") (name "unconnected-(P1-TX-Pad35)") (class "Default")
      (node (ref "P1") (pin "35") (pinfunction "TX_35") (pintype "unspecified+no_connect"))
    )
    (net (code "112") (name "unconnected-(P1-TX2-Pad75)") (class "Default")
      (node (ref "P1") (pin "75") (pinfunction "TX2_75") (pintype "unspecified+no_connect"))
    )
    (net (code "113") (name "unconnected-(P1-{slash}BUSACK-Pad62)") (class "Default")
      (node (ref "P1") (pin "62") (pinfunction "/BUSACK_62") (pintype "unspecified+no_connect"))
    )
    (net (code "114") (name "unconnected-(P1-{slash}BUSRQ-Pad64)") (class "Default")
      (node (ref "P1") (pin "64") (pinfunction "/BUSRQ_64") (pintype "unspecified+no_connect"))
    )
    (net (code "115") (name "unconnected-(P1-{slash}HALT-Pad63)") (class "Default")
      (node (ref "P1") (pin "63") (pinfunction "/HALT_63") (pintype "unspecified+no_connect"))
    )
    (net (code "116") (name "unconnected-(P1-{slash}INT-Pad22)") (class "Default")
      (node (ref "P1") (pin "22") (pinfunction "/INT_22") (pintype "unspecified+no_connect"))
    )
    (net (code "117") (name "unconnected-(P1-{slash}IORQ-Pad26)") (class "Default")
      (node (ref "P1") (pin "26") (pinfunction "/IORQ_26") (pintype "unspecified+no_connect"))
    )
    (net (code "118") (name "unconnected-(P1-{slash}M1-Pad19)") (class "Default")
      (node (ref "P1") (pin "19") (pinfunction "/M1_19") (pintype "unspecified+no_connect"))
    )
    (net (code "119") (name "unconnected-(P1-{slash}MREQ-Pad23)") (class "Default")
      (node (ref "P1") (pin "23") (pinfunction "/MREQ_23") (pintype "unspecified+no_connect"))
    )
    (net (code "120") (name "unconnected-(P1-{slash}NMI-Pad66)") (class "Default")
      (node (ref "P1") (pin "66") (pinfunction "/NMI_66") (pintype "unspecified+no_connect"))
    )
    (net (code "121") (name "unconnected-(P1-{slash}RD-Pad25)") (class "Default")
      (node (ref "P1") (pin "25") (pinfunction "/RD_25") (pintype "unspecified+no_connect"))
    )
    (net (code "122") (name "unconnected-(P1-{slash}RESET-Pad20)") (class "Default")
      (node (ref "P1") (pin "20") (pinfunction "/RESET_20") (pintype "unspecified+no_connect"))
    )
    (net (code "123") (name "unconnected-(P1-{slash}RFSH-Pad59)") (class "Default")
      (node (ref "P1") (pin "59") (pinfunction "/RFSH_59") (pintype "unspecified+no_connect"))
    )
    (net (code "124") (name "unconnected-(P1-{slash}WAIT-Pad65)") (class "Default")
      (node (ref "P1") (pin "65") (pinfunction "/WAIT_65") (pintype "unspecified+no_connect"))
    )
    (net (code "125") (name "unconnected-(P1-{slash}WR-Pad24)") (class "Default")
      (node (ref "P1") (pin "24") (pinfunction "/WR_24") (pintype "unspecified+no_connect"))
    )
    (net (code "126") (name "unconnected-(U1-INTA-Pad20)") (class "Default")
      (node (ref "U1") (pin "20") (pinfunction "INTA_20") (pintype "unspecified+no_connect"))
    )
    (net (code "127") (name "unconnected-(U1-INTB-Pad19)") (class "Default")
      (node (ref "U1") (pin "19") (pinfunction "INTB_19") (pintype "unspecified+no_connect"))
    )
    (net (code "128") (name "unconnected-(U1-NC-Pad11)") (class "Default")
      (node (ref "U1") (pin "11") (pinfunction "NC_11") (pintype "unspecified+no_connect"))
    )
    (net (code "129") (name "unconnected-(U1-NC-Pad14)") (class "Default")
      (node (ref "U1") (pin "14") (pinfunction "NC_14") (pintype "unspecified+no_connect"))
    )
    (net (code "130") (name "{slash}ACK") (class "Default")
      (node (ref "PRINTER") (pin "10") (pinfunction "10_10") (pintype "unspecified"))
      (node (ref "R28") (pin "1") (pinfunction "1_1") (pintype "unspecified"))
      (node (ref "U2") (pin "8") (pinfunction "1A4_8") (pintype "unspecified"))
    )
    (net (code "131") (name "{slash}AUTOFD") (class "Default")
      (node (ref "PRINTER") (pin "14") (pinfunction "14_14") (pintype "unspecified"))
      (node (ref "R10") (pin "2") (pinfunction "2_2") (pintype "unspecified"))
    )
    (net (code "132") (name "{slash}ERROR") (class "Default")
      (node (ref "PRINTER") (pin "15") (pinfunction "15_15") (pintype "unspecified"))
      (node (ref "R24") (pin "1") (pinfunction "1_1") (pintype "unspecified"))
      (node (ref "U2") (pin "17") (pinfunction "2A4_17") (pintype "unspecified"))
    )
    (net (code "133") (name "{slash}INIT") (class "Default")
      (node (ref "PRINTER") (pin "16") (pinfunction "16_16") (pintype "unspecified"))
      (node (ref "R11") (pin "2") (pinfunction "2_2") (pintype "unspecified"))
    )
    (net (code "134") (name "{slash}STROBE") (class "Default")
      (node (ref "PRINTER") (pin "1") (pinfunction "1_1") (pintype "unspecified"))
      (node (ref "R9") (pin "2") (pinfunction "2_2") (pintype "unspecified"))
    )
  )
)
